# Microcontroller.net
KiCad netlist of a schematic drawn in Altium Designer
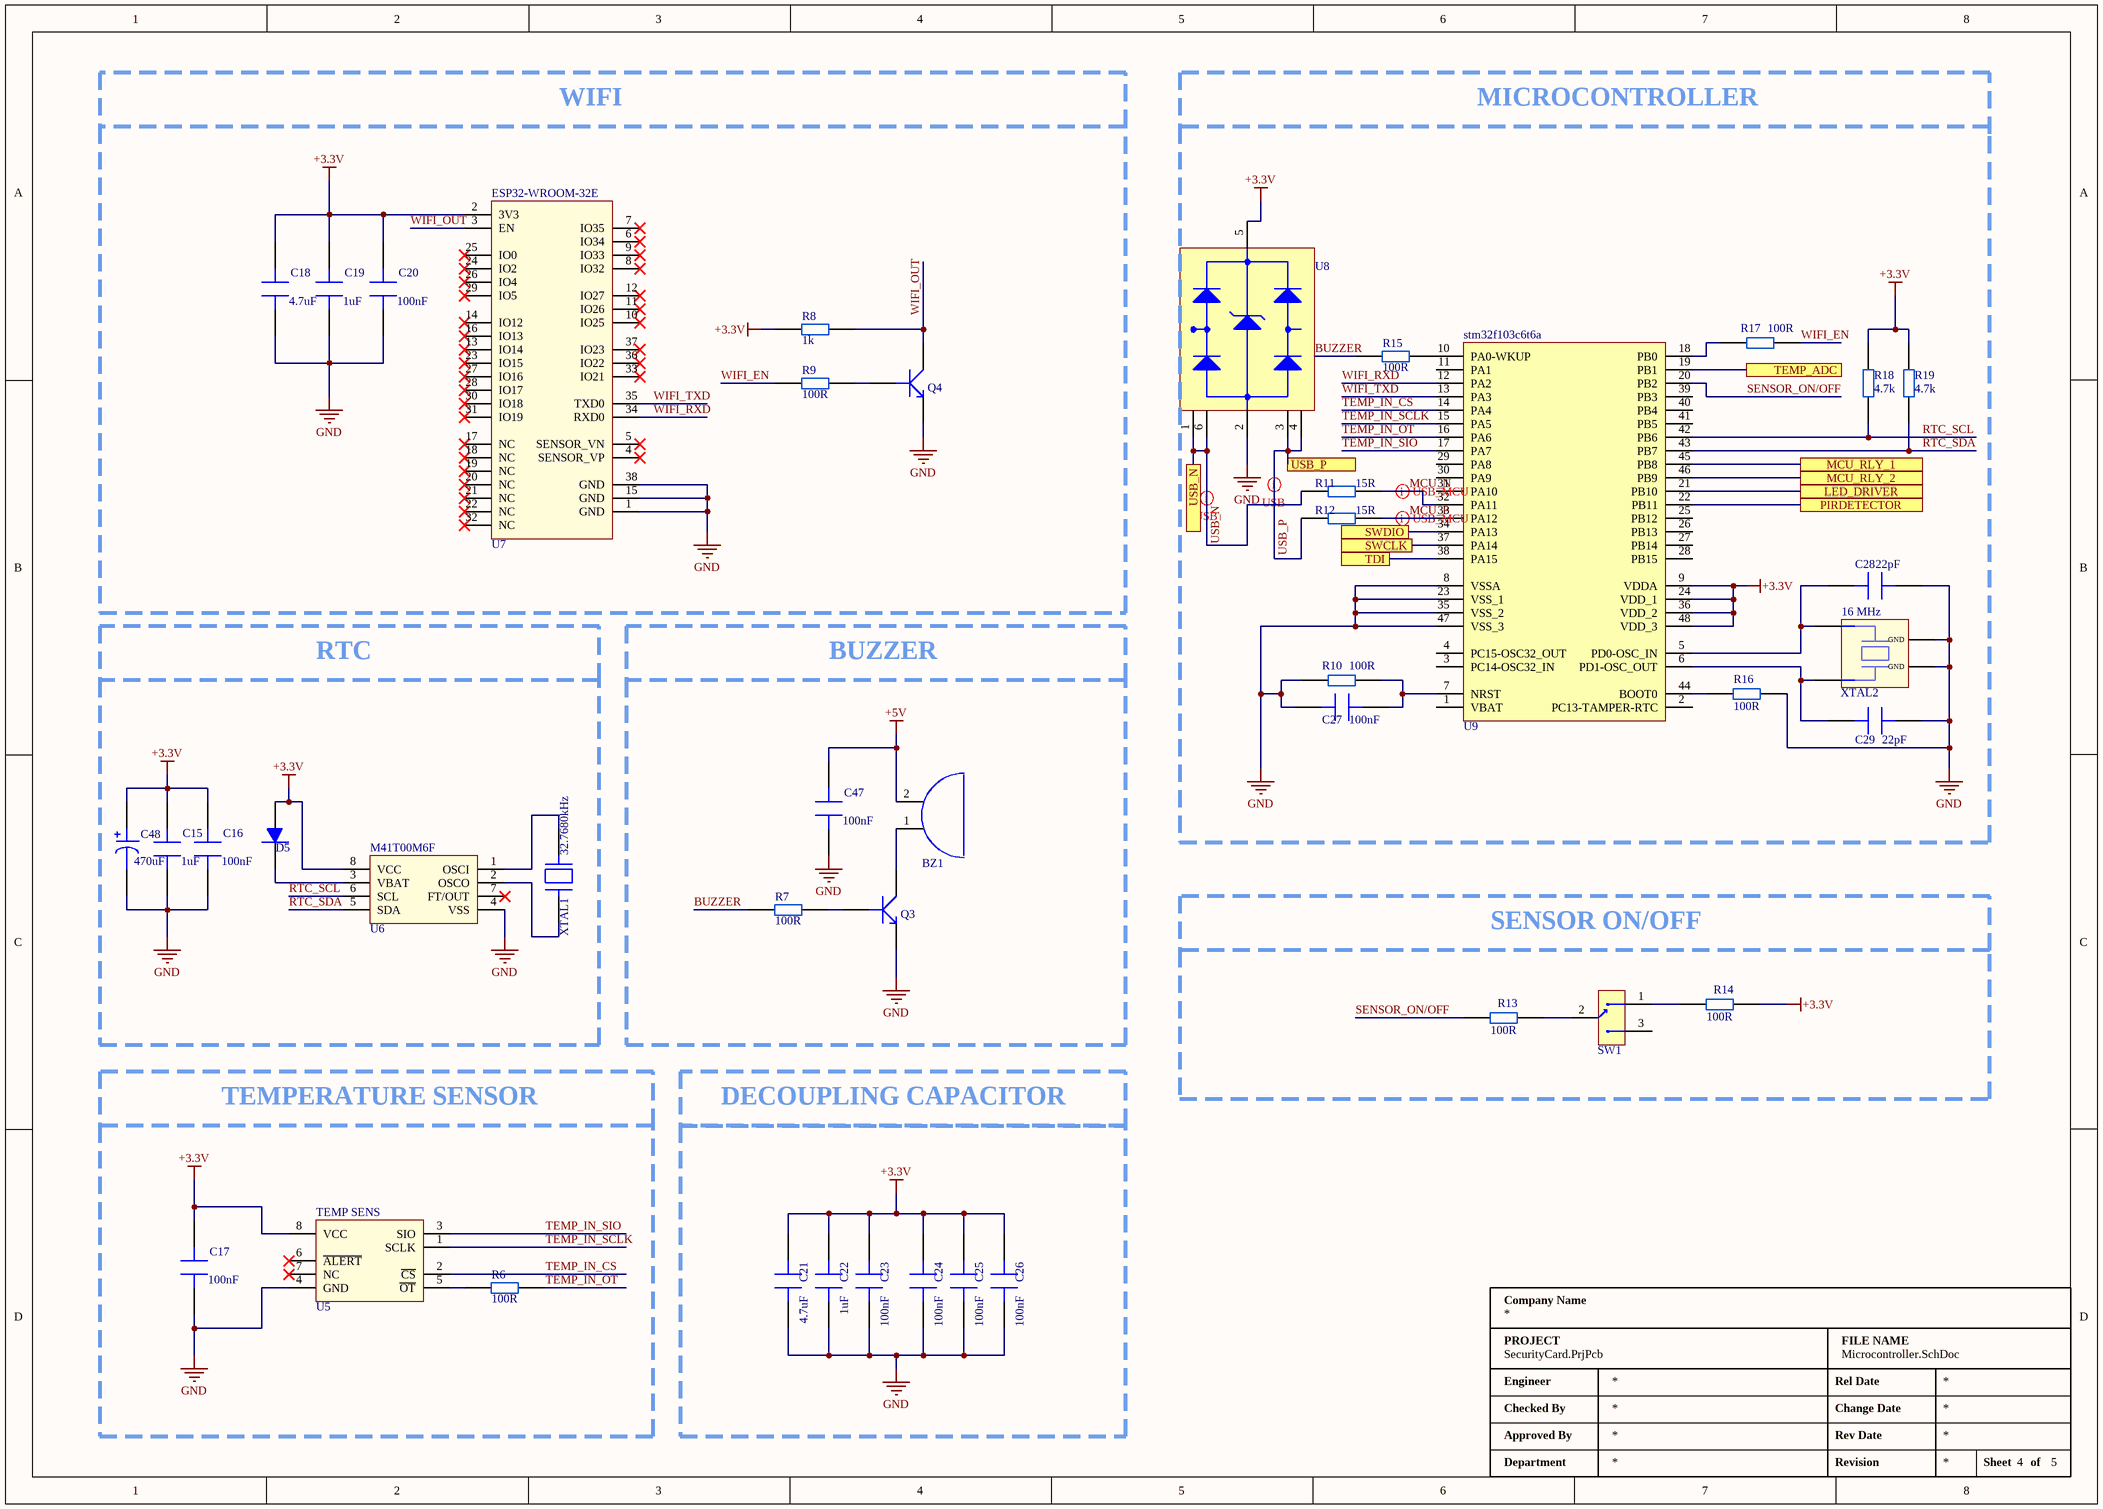
[diagram p0: Microcontroller.SchDoc]

(export (version "E")
  (design (tool "Eeschema 10.0.6"))
  (components
    (comp (ref "BZ1")
      (value "CMI-9605-0580T")
      (footprint "BUZZER")
      (description "9.6 mm, 5 Vdc, 80 dB, Through Hole, Driving Circuit, Magnetic Audio Indicator Buzzer")
      (fields (field (name "MANUFACTURER") "CUI") (field (name "DESIGNED BY") "SEFA"))
      (libsource (lib "SecurityLibray") (part "CMI-9605-0580T"))
    )
    (comp (ref "C15")
      (value "1uF")
      (footprint "CAP 0805")
      (description "Multilayer Ceramic Capacitor, 1 uF, 25 V, ï¿½ 10%, X7R, 0805 [2012 Metric]")
      (fields
        (field (name "MANUFACTURER") "KEMET")
        (field (name "MANUFACTURER PART NUMBER") "C0805C105K3RACTU")
      )
      (libsource (lib "SecurityLibray") (part "CAP MLCC 1uF 0805 MLCC"))
    )
    (comp (ref "C16")
      (value "100nF")
      (footprint "CAP 0805")
      (description "Multilayer Ceramic Capacitor, 0.1 uF, 50 V, ± 10%, X7R, 0805 [2012 Metric]")
      (fields
        (field (name "MANUFACTURER") "Yageo")
        (field (name "MANUFACTURER PART NUMBER") "CC0805KRX7R9BB104")
      )
      (libsource (lib "SecurityLibray") (part "CAP MLCC 100nF 0805"))
    )
    (comp (ref "C17")
      (value "100nF")
      (footprint "CAP 0603")
      (description "Multilayer Ceramic Capacitor, 0.1 uF, 50 V, ± 10%, X7R, 0603 [1608 Metric]")
      (fields
        (field (name "MANUFACTURER") "Kyocera AVX")
        (field (name "MANUFACTURER PART NUMBER") "06035C104K4T2A")
        (field (name "DESIGNED BY") "SEFA")
      )
      (libsource (lib "SecurityLibray") (part "CAP MLCC 100nF 0603"))
    )
    (comp (ref "C18")
      (value "4.7uF")
      (footprint "CAP 0805")
      (description "Multilayer Ceramic Capacitor, 4.7 uF, 25 V, ± 10%, X5R, 0805 [2012 Metric]")
      (fields
        (field (name "MANUFACTURER") "Samsung")
        (field (name "MANUFACTURER PART NUMBER") "CL21A475KAQNNNE")
        (field (name "DESIGNED BY") "SEFA")
      )
      (libsource (lib "SecurityLibray") (part "CAP MLCC 4.7uF 0805 MLCC"))
    )
    (comp (ref "C19")
      (value "1uF")
      (footprint "CAP 0805")
      (description "Multilayer Ceramic Capacitor, 1 uF, 25 V, ï¿½ 10%, X7R, 0805 [2012 Metric]")
      (fields
        (field (name "MANUFACTURER") "KEMET")
        (field (name "MANUFACTURER PART NUMBER") "C0805C105K3RACTU")
      )
      (libsource (lib "SecurityLibray") (part "CAP MLCC 1uF 0805 MLCC"))
    )
    (comp (ref "C20")
      (value "100nF")
      (footprint "CAP 0805")
      (description "Multilayer Ceramic Capacitor, 0.1 uF, 50 V, ± 10%, X7R, 0805 [2012 Metric]")
      (fields
        (field (name "MANUFACTURER") "Yageo")
        (field (name "MANUFACTURER PART NUMBER") "CC0805KRX7R9BB104")
      )
      (libsource (lib "SecurityLibray") (part "CAP MLCC 100nF 0805"))
    )
    (comp (ref "C21")
      (value "4.7uF")
      (footprint "CAP 0805")
      (description "Multilayer Ceramic Capacitor, 4.7 uF, 25 V, ± 10%, X5R, 0805 [2012 Metric]")
      (fields
        (field (name "MANUFACTURER") "Samsung")
        (field (name "MANUFACTURER PART NUMBER") "CL21A475KAQNNNE")
        (field (name "DESIGNED BY") "SEFA")
      )
      (libsource (lib "SecurityLibray") (part "CAP MLCC 4.7uF 0805 MLCC"))
    )
    (comp (ref "C22")
      (value "1uF")
      (footprint "CAP 0805")
      (description "Multilayer Ceramic Capacitor, 1 uF, 25 V, ï¿½ 10%, X7R, 0805 [2012 Metric]")
      (fields
        (field (name "MANUFACTURER") "KEMET")
        (field (name "MANUFACTURER PART NUMBER") "C0805C105K3RACTU")
      )
      (libsource (lib "SecurityLibray") (part "CAP MLCC 1uF 0805 MLCC"))
    )
    (comp (ref "C23")
      (value "100nF")
      (footprint "CAP 0805")
      (description "Multilayer Ceramic Capacitor, 0.1 uF, 50 V, ± 10%, X7R, 0805 [2012 Metric]")
      (fields
        (field (name "MANUFACTURER") "Yageo")
        (field (name "MANUFACTURER PART NUMBER") "CC0805KRX7R9BB104")
      )
      (libsource (lib "SecurityLibray") (part "CAP MLCC 100nF 0805"))
    )
    (comp (ref "C24")
      (value "100nF")
      (footprint "CAP 0805")
      (description "Multilayer Ceramic Capacitor, 0.1 uF, 50 V, ± 10%, X7R, 0805 [2012 Metric]")
      (fields
        (field (name "MANUFACTURER") "Yageo")
        (field (name "MANUFACTURER PART NUMBER") "CC0805KRX7R9BB104")
      )
      (libsource (lib "SecurityLibray") (part "CAP MLCC 100nF 0805"))
    )
    (comp (ref "C25")
      (value "100nF")
      (footprint "CAP 0805")
      (description "Multilayer Ceramic Capacitor, 0.1 uF, 50 V, ± 10%, X7R, 0805 [2012 Metric]")
      (fields
        (field (name "MANUFACTURER") "Yageo")
        (field (name "MANUFACTURER PART NUMBER") "CC0805KRX7R9BB104")
      )
      (libsource (lib "SecurityLibray") (part "CAP MLCC 100nF 0805"))
    )
    (comp (ref "C26")
      (value "100nF")
      (footprint "CAP 0805")
      (description "Multilayer Ceramic Capacitor, 0.1 uF, 50 V, ± 10%, X7R, 0805 [2012 Metric]")
      (fields
        (field (name "MANUFACTURER") "Yageo")
        (field (name "MANUFACTURER PART NUMBER") "CC0805KRX7R9BB104")
      )
      (libsource (lib "SecurityLibray") (part "CAP MLCC 100nF 0805"))
    )
    (comp (ref "C27")
      (value "100nF")
      (footprint "CAP 0805")
      (description "Multilayer Ceramic Capacitor, 0.1 uF, 50 V, ± 10%, X7R, 0805 [2012 Metric]")
      (fields
        (field (name "MANUFACTURER") "Yageo")
        (field (name "MANUFACTURER PART NUMBER") "CC0805KRX7R9BB104")
      )
      (libsource (lib "SecurityLibray") (part "CAP MLCC 100nF 0805"))
    )
    (comp (ref "C28")
      (value "22pF")
      (footprint "CAP 0603")
      (description "Multilayer Ceramic Capacitor, 22 pF, 50 V, ï¿½ 5%, C0G (NP0), 0603 [1608 Metric]")
      (fields
        (field (name "MANUFACTURER") "KEMET")
        (field (name "MANUFACTURER PART NUMBER") "C0603C220J5GACTU")
        (field (name "DESIGNED BY") "SEFA")
      )
      (libsource (lib "SecurityLibray") (part "CAP MLCC 22pF 0603"))
    )
    (comp (ref "C29")
      (value "22pF")
      (footprint "CAP 0603")
      (description "Multilayer Ceramic Capacitor, 22 pF, 50 V, ï¿½ 5%, C0G (NP0), 0603 [1608 Metric]")
      (fields
        (field (name "MANUFACTURER") "KEMET")
        (field (name "MANUFACTURER PART NUMBER") "C0603C220J5GACTU")
        (field (name "DESIGNED BY") "SEFA")
      )
      (libsource (lib "SecurityLibray") (part "CAP MLCC 22pF 0603"))
    )
    (comp (ref "C47")
      (value "100nF")
      (footprint "CAP 0805")
      (description "Multilayer Ceramic Capacitor, 0.1 uF, 50 V, ± 10%, X7R, 0805 [2012 Metric]")
      (fields
        (field (name "MANUFACTURER") "Yageo")
        (field (name "MANUFACTURER PART NUMBER") "CC0805KRX7R9BB104")
      )
      (libsource (lib "SecurityLibray") (part "CAP MLCC 100nF 0805"))
    )
    (comp (ref "C48")
      (value "470uF")
      (footprint "CAP ALUM 470UF 20% 50V RADIAL TH")
      (description "Aluminum Electrolytic Capacitor, 470 uF, 63 V, ± 20%, 8000 hours @ 85°C, Axial Leaded")
      (fields
        (field (name "MANUFACTURER") "Vishay BCcomponents")
        (field (name "MANUFACTURER PART NUMBER") "MAL202118471E3")
      )
      (libsource (lib "SecurityLibray") (part "470uF ECAP CA-1HM471"))
    )
    (comp (ref "D5")
      (value "DIODE GEN PURP 75V 150MA SOD323F")
      (footprint "DIODE SOD323F")
      (description "Diode Ultra Fast Recovery Rectifier 75V 0.15A 2-Pin SOD-323F T/R")
      (fields
        (field (name "MANUFACTURER") "ON Semiconductor / Fairchild")
        (field (name "MANUFACTURER PART NUMBER") "1N4148WS")
      )
      (libsource (lib "SecurityLibray") (part "DIODE 1N4148WS"))
    )
    (comp (ref "Q3")
      (value "TRANS NPN 40V 0.2A SOT23")
      (footprint "SOT-23-3")
      (description "Transistor: NPN; bipolar; 40V; 0.2A; 350mW; -55+150 deg.C; SMD; SOT23")
      (fields
        (field (name "MANUFACTURER") "Diotec")
        (field (name "MANUFACTURER PART NUMBER") "MMBT3904")
        (field (name "DESIGNED BY") "SEFA")
      )
      (libsource (lib "SecurityLibray") (part "MMBT3904 NPN TR"))
    )
    (comp (ref "Q4")
      (value "TRANS NPN 40V 0.2A SOT23")
      (footprint "SOT-23-3")
      (description "Transistor: NPN; bipolar; 40V; 0.2A; 350mW; -55+150 deg.C; SMD; SOT23")
      (fields
        (field (name "MANUFACTURER") "Diotec")
        (field (name "MANUFACTURER PART NUMBER") "MMBT3904")
        (field (name "DESIGNED BY") "SEFA")
      )
      (libsource (lib "SecurityLibray") (part "MMBT3904 NPN TR"))
    )
    (comp (ref "R6")
      (value "100R")
      (footprint "RES 0603")
      (description "Res Thick Film 0603 10K Ohm 5% 1/10W ±100ppm/°C Molded SMD SMD Paper T/R")
      (fields
        (field (name "MANUFACTURER") "Stackpole Electronics")
        (field (name "MANUFACTURER PART NUMBER") "RMCF0603JT10K0")
        (field (name "DESIGNED BY") "SEFA")
      )
      (libsource (lib "SecurityLibray") (part "RES 10K OHM 0603"))
    )
    (comp (ref "R7")
      (value "100R")
      (footprint "RES 0603")
      (description "Res Thick Film 0603 10K Ohm 5% 1/10W ±100ppm/°C Molded SMD SMD Paper T/R")
      (fields
        (field (name "MANUFACTURER") "Stackpole Electronics")
        (field (name "MANUFACTURER PART NUMBER") "RMCF0603JT10K0")
        (field (name "DESIGNED BY") "SEFA")
      )
      (libsource (lib "SecurityLibray") (part "RES 10K OHM 0603"))
    )
    (comp (ref "R8")
      (value "1k")
      (footprint "RES 0603")
      (description "Res Thick Film 0603 10K Ohm 5% 1/10W ±100ppm/°C Molded SMD SMD Paper T/R")
      (fields
        (field (name "MANUFACTURER") "Stackpole Electronics")
        (field (name "MANUFACTURER PART NUMBER") "RMCF0603JT10K0")
        (field (name "DESIGNED BY") "SEFA")
      )
      (libsource (lib "") (part "RES 10K OHM 0603_2"))
    )
    (comp (ref "R9")
      (value "100R")
      (footprint "RES 0603")
      (description "Res Thick Film 0603 10K Ohm 5% 1/10W ±100ppm/°C Molded SMD SMD Paper T/R")
      (fields
        (field (name "MANUFACTURER") "Stackpole Electronics")
        (field (name "MANUFACTURER PART NUMBER") "RMCF0603JT10K0")
        (field (name "DESIGNED BY") "SEFA")
      )
      (libsource (lib "SecurityLibray") (part "RES 10K OHM 0603"))
    )
    (comp (ref "R10")
      (value "100R")
      (footprint "RES 0603")
      (description "Res Thick Film 0603 10K Ohm 5% 1/10W ±100ppm/°C Molded SMD SMD Paper T/R")
      (fields
        (field (name "MANUFACTURER") "Stackpole Electronics")
        (field (name "MANUFACTURER PART NUMBER") "RMCF0603JT10K0")
        (field (name "DESIGNED BY") "SEFA")
      )
      (libsource (lib "") (part "RES 10K OHM 0603_2"))
    )
    (comp (ref "R11")
      (value "15R")
      (footprint "RES 0603")
      (description "Res Thick Film 0603 15 Ohm 1% 0.1W(1/10W) ±100ppm/C Pad SMD Automotive T/R")
      (fields
        (field (name "MANUFACTURER") "Stackpole Electronics")
        (field (name "MANUFACTURER PART NUMBER") "RMCF0603FT15R0")
        (field (name "DESIGNED BY") "SEFA")
      )
      (libsource (lib "SecurityLibray") (part "RES 15R OHM 0603"))
    )
    (comp (ref "R12")
      (value "15R")
      (footprint "RES 0603")
      (description "Res Thick Film 0603 15 Ohm 1% 0.1W(1/10W) ±100ppm/C Pad SMD Automotive T/R")
      (fields
        (field (name "MANUFACTURER") "Stackpole Electronics")
        (field (name "MANUFACTURER PART NUMBER") "RMCF0603FT15R0")
        (field (name "DESIGNED BY") "SEFA")
      )
      (libsource (lib "SecurityLibray") (part "RES 15R OHM 0603"))
    )
    (comp (ref "R13")
      (value "100R")
      (footprint "RES 0603")
      (description "GENERAL PURPOSE CHIP RESISTOR Metal Glaze/thick Film, 0.1W, 0ohm, Surface Mount, 0603")
      (fields
        (field (name "MANUFACTURER") "Yageo")
        (field (name "MANUFACTURER PART NUMBER") "RC0603JR-070RL")
        (field (name "DESIGNED BY") "SEFA")
      )
      (libsource (lib "SecurityLibray") (part "RES 0R OHM 0603"))
    )
    (comp (ref "R14")
      (value "100R")
      (footprint "RES 0603")
      (description "GENERAL PURPOSE CHIP RESISTOR Metal Glaze/thick Film, 0.1W, 0ohm, Surface Mount, 0603")
      (fields
        (field (name "MANUFACTURER") "Yageo")
        (field (name "MANUFACTURER PART NUMBER") "RC0603JR-070RL")
        (field (name "DESIGNED BY") "SEFA")
      )
      (libsource (lib "SecurityLibray") (part "RES 0R OHM 0603"))
    )
    (comp (ref "R15")
      (value "100R")
      (footprint "RES 0603")
      (description "Res Thick Film 0603 10K Ohm 5% 1/10W ±100ppm/°C Molded SMD SMD Paper T/R")
      (fields
        (field (name "MANUFACTURER") "Stackpole Electronics")
        (field (name "MANUFACTURER PART NUMBER") "RMCF0603JT10K0")
        (field (name "DESIGNED BY") "SEFA")
      )
      (libsource (lib "SecurityLibray") (part "RES 10K OHM 0603"))
    )
    (comp (ref "R16")
      (value "100R")
      (footprint "RES 0603")
      (description "Res Thick Film 0603 10K Ohm 5% 1/10W ±100ppm/°C Molded SMD SMD Paper T/R")
      (fields
        (field (name "MANUFACTURER") "Stackpole Electronics")
        (field (name "MANUFACTURER PART NUMBER") "RMCF0603JT10K0")
        (field (name "DESIGNED BY") "SEFA")
      )
      (libsource (lib "") (part "RES 10K OHM 0603_2"))
    )
    (comp (ref "R17")
      (value "100R")
      (footprint "RES 0603")
      (description "Res Thick Film 0603 10K Ohm 5% 1/10W ±100ppm/°C Molded SMD SMD Paper T/R")
      (fields
        (field (name "MANUFACTURER") "Stackpole Electronics")
        (field (name "MANUFACTURER PART NUMBER") "RMCF0603JT10K0")
        (field (name "DESIGNED BY") "SEFA")
      )
      (libsource (lib "") (part "RES 10K OHM 0603_2"))
    )
    (comp (ref "R18")
      (value "4.7k")
      (footprint "RES 0603")
      (description "Res Thick Film 0603 10K Ohm 5% 1/10W ±100ppm/°C Molded SMD SMD Paper T/R")
      (fields
        (field (name "MANUFACTURER") "Stackpole Electronics")
        (field (name "MANUFACTURER PART NUMBER") "RMCF0603JT10K0")
        (field (name "DESIGNED BY") "SEFA")
      )
      (libsource (lib "") (part "RES 10K OHM 0603_1"))
    )
    (comp (ref "R19")
      (value "4.7k")
      (footprint "RES 0603")
      (description "Res Thick Film 0603 10K Ohm 5% 1/10W ±100ppm/°C Molded SMD SMD Paper T/R")
      (fields
        (field (name "MANUFACTURER") "Stackpole Electronics")
        (field (name "MANUFACTURER PART NUMBER") "RMCF0603JT10K0")
        (field (name "DESIGNED BY") "SEFA")
      )
      (libsource (lib "") (part "RES 10K OHM 0603_1"))
    )
    (comp (ref "SW1")
      (value "EG1215AA")
      (footprint "EG1215AA")
      (description "Slide Switch, SPDT, 0.025A, 24V, SMD")
      (fields (field (name "MANUFACTURER") "E-Switch") (field (name "DESIGNED BY") "SEFA"))
      (libsource (lib "SecurityLibray") (part "EG1215AA"))
    )
    (comp (ref "U5")
      (value "TEMP SENS")
      (footprint "SOIC8")
      (description "Temp Sensor Digital Serial (3-Wire, SPI) 8-Pin SOIC N Tube")
      (fields
        (field (name "MANUFACTURER") "Maxim")
        (field (name "MANUFACTURER PART NUMBER") "MAX6662MSA+")
        (field (name "DESIGNED BY") "SEFA")
      )
      (libsource (lib "SecurityLibray") (part "MAX6662"))
    )
    (comp (ref "U6")
      (value "M41T00M6F")
      (footprint "SOIC8")
      (description "Low-power serial real-time clock (RTC) with built-in battery switchover circuit")
      (fields
        (field (name "MANUFACTURER") "STMicroelectronics")
        (field (name "MANUFACTURER PART NUMBER") "M41T01M6F")
        (field (name "DESIGNED BY") "SEFA")
      )
      (libsource (lib "SecurityLibray") (part "M41T00M6F"))
    )
    (comp (ref "U7")
      (value "ESP32-WROOM-32E")
      (footprint "ESP32 WROOM 4MB")
      (description "SMD module, ESP32-D0WD-V3, ESP32 ECO V3, 4 MB SPI flash, PCB antenna")
      (fields
        (field (name "MANUFACTURER") "Espressif Systems")
        (field (name "MANUFACTURER PART NUMBER") "ESP32-WROOM-32E(M113EH3200PH3Q0)")
        (field (name "DESIGNED BY") "SEFA")
      )
      (libsource (lib "SecurityLibray") (part "ESP32-WROOM-32E(4MB)"))
    )
    (comp (ref "U8")
      (value "TVS DIODE 5.25VWM 17VC SOT23-6")
      (footprint "SOT23-6")
      (description "ESD Suppressor Diode Arrays Uni-Dir 15kV@Air Gap/8kV@Contact Disc 6-Pin SOT-23 T/R")
      (fields
        (field (name "MANUFACTURER") "STMicroelectronics")
        (field (name "MANUFACTURER PART NUMBER") "USBLC6-2SC6Y")
        (field (name "DESIGNED BY") "SEFA")
      )
      (libsource (lib "SecurityLibray") (part "DIODE TVS USB PRODECTION"))
    )
    (comp (ref "U9")
      (value "stm32f103c6t6a")
      (footprint "LQFP-48")
      (description "MCU 32-bit STM32F ARM Cortex M3 RISC 32KB Flash 2.5V/3.3V 48-Pin LQFP Tray")
      (fields
        (field (name "MANUFACTURER") "STMicroelectronics")
        (field (name "MANUFACTURER PART NUMBER") "STM32F103C6T6A")
        (field (name "DESIGNED BY") "SEFA")
      )
      (libsource (lib "SecurityLibray") (part "stm32f103c6t6a"))
    )
    (comp (ref "XTAL1")
      (value "32.7680kHz")
      (footprint "CRYSTALL 2SMD")
      (description "Crystal 0.032768MHz ±20ppm (Tol) 12.5pF Flexural 90000Ohm 2-Pin CSMD T/R")
      (fields
        (field (name "MANUFACTURER") "Abracon")
        (field (name "MANUFACTURER PART NUMBER") "ABS05-32.768KHZ-T")
        (field (name "DESIGNED BY") "SEFA")
      )
      (libsource (lib "SecurityLibray") (part "RTC CRYS ABS05-32.768KHZ-T"))
    )
    (comp (ref "XTAL2")
      (value "16 MHz")
      (footprint "CRYSTAL 16MHz 4SMD")
      (description "Crystal 16MHz ±30ppm (Tol) ±50ppm (Stability) 20pF FUND 50Ohm 4-Pin Mini-SMD T/R")
      (fields
        (field (name "MANUFACTURER") "ECS International")
        (field (name "MANUFACTURER PART NUMBER") "ECS-160-20-30B-TR")
        (field (name "DESIGNED BY") "SEFA")
      )
      (libsource (lib "SecurityLibray") (part "CRYSTAL 16MHz ECS-160-20-30B-TR"))
    )
  )
  (nets
    (net (code "1") (name "+3.3V") (class "Default")
      (node (ref "C15") (pin "2") (pinfunction "2_2") (pintype "passive"))
      (node (ref "C16") (pin "2") (pinfunction "2_2") (pintype "passive"))
      (node (ref "C17") (pin "2") (pinfunction "2_2") (pintype "passive"))
      (node (ref "C18") (pin "2") (pinfunction "2_2") (pintype "passive"))
      (node (ref "C19") (pin "2") (pinfunction "2_2") (pintype "passive"))
      (node (ref "C20") (pin "2") (pinfunction "2_2") (pintype "passive"))
      (node (ref "C21") (pin "2") (pinfunction "2_2") (pintype "passive"))
      (node (ref "C22") (pin "2") (pinfunction "2_2") (pintype "passive"))
      (node (ref "C23") (pin "2") (pinfunction "2_2") (pintype "passive"))
      (node (ref "C24") (pin "2") (pinfunction "2_2") (pintype "passive"))
      (node (ref "C25") (pin "2") (pinfunction "2_2") (pintype "passive"))
      (node (ref "C26") (pin "2") (pinfunction "2_2") (pintype "passive"))
      (node (ref "C48") (pin "1") (pinfunction "1_1") (pintype "passive"))
      (node (ref "D5") (pin "A") (pinfunction "1_A") (pintype "passive"))
      (node (ref "R14") (pin "2") (pinfunction "2_2") (pintype "passive"))
      (node (ref "R18") (pin "2") (pinfunction "2_2") (pintype "passive"))
      (node (ref "R19") (pin "2") (pinfunction "2_2") (pintype "passive"))
      (node (ref "R8") (pin "2") (pinfunction "2_2") (pintype "passive"))
      (node (ref "U5") (pin "8") (pinfunction "VCC_8") (pintype "passive"))
      (node (ref "U6") (pin "8") (pinfunction "VCC_8") (pintype "passive"))
      (node (ref "U7") (pin "2") (pinfunction "3V3_2") (pintype "passive"))
      (node (ref "U8") (pin "5") (pinfunction "VBUS_5") (pintype "power_in"))
      (node (ref "U9") (pin "24") (pinfunction "VDD_1_24") (pintype "passive"))
      (node (ref "U9") (pin "36") (pinfunction "VDD_2_36") (pintype "passive"))
      (node (ref "U9") (pin "48") (pinfunction "VDD_3_48") (pintype "passive"))
      (node (ref "U9") (pin "9") (pinfunction "VDDA_9") (pintype "passive"))
    )
    (net (code "2") (name "+5V") (class "Default")
      (node (ref "BZ1") (pin "2") (pinfunction "2_2") (pintype "passive"))
      (node (ref "C47") (pin "2") (pinfunction "2_2") (pintype "passive"))
    )
    (net (code "3") (name "/BUZZER") (class "Default")
      (node (ref "R15") (pin "1") (pinfunction "1_1") (pintype "passive"))
      (node (ref "R7") (pin "1") (pinfunction "1_1") (pintype "passive"))
    )
    (net (code "4") (name "/LED_DRIVER") (class "Default")
      (node (ref "U9") (pin "21") (pinfunction "PB10_21") (pintype "passive"))
    )
    (net (code "5") (name "/MCU_N") (class "Default")
      (node (ref "R11") (pin "2") (pinfunction "2_2") (pintype "passive"))
      (node (ref "U9") (pin "32") (pinfunction "PA11_32") (pintype "passive"))
    )
    (net (code "6") (name "/MCU_P") (class "Default")
      (node (ref "R12") (pin "2") (pinfunction "2_2") (pintype "passive"))
      (node (ref "U9") (pin "33") (pinfunction "PA12_33") (pintype "passive"))
    )
    (net (code "7") (name "/MCU_RLY_1") (class "Default")
      (node (ref "U9") (pin "45") (pinfunction "PB8_45") (pintype "passive"))
    )
    (net (code "8") (name "/MCU_RLY_2") (class "Default")
      (node (ref "U9") (pin "46") (pinfunction "PB9_46") (pintype "passive"))
    )
    (net (code "9") (name "/PIRDETECTOR") (class "Default")
      (node (ref "U9") (pin "22") (pinfunction "PB11_22") (pintype "passive"))
    )
    (net (code "10") (name "/RTC_SCL") (class "Default")
      (node (ref "R18") (pin "1") (pinfunction "1_1") (pintype "passive"))
      (node (ref "U6") (pin "6") (pinfunction "SCL_6") (pintype "passive"))
      (node (ref "U9") (pin "42") (pinfunction "PB6_42") (pintype "passive"))
    )
    (net (code "11") (name "/RTC_SDA") (class "Default")
      (node (ref "R19") (pin "1") (pinfunction "1_1") (pintype "passive"))
      (node (ref "U6") (pin "5") (pinfunction "SDA_5") (pintype "passive"))
      (node (ref "U9") (pin "43") (pinfunction "PB7_43") (pintype "passive"))
    )
    (net (code "12") (name "/SENSOR_ON{slash}OFF") (class "Default")
      (node (ref "R13") (pin "1") (pinfunction "1_1") (pintype "passive"))
      (node (ref "U9") (pin "20") (pinfunction "PB2_20") (pintype "passive"))
    )
    (net (code "13") (name "/SWCLK") (class "Default")
      (node (ref "U9") (pin "37") (pinfunction "PA14_37") (pintype "passive"))
    )
    (net (code "14") (name "/SWDIO") (class "Default")
      (node (ref "U9") (pin "34") (pinfunction "PA13_34") (pintype "passive"))
    )
    (net (code "15") (name "/TDI") (class "Default")
      (node (ref "U9") (pin "38") (pinfunction "PA15_38") (pintype "passive"))
    )
    (net (code "16") (name "/TEMP_ADC") (class "Default")
      (node (ref "U9") (pin "19") (pinfunction "PB1_19") (pintype "passive"))
    )
    (net (code "17") (name "/TEMP_IN_CS") (class "Default")
      (node (ref "U5") (pin "2") (pinfunction "~{CS}_2") (pintype "passive"))
      (node (ref "U9") (pin "14") (pinfunction "PA4_14") (pintype "passive"))
    )
    (net (code "18") (name "/TEMP_IN_OT") (class "Default")
      (node (ref "R6") (pin "2") (pinfunction "2_2") (pintype "passive"))
      (node (ref "U9") (pin "16") (pinfunction "PA6_16") (pintype "passive"))
    )
    (net (code "19") (name "/TEMP_IN_SCLK") (class "Default")
      (node (ref "U5") (pin "1") (pinfunction "SCLK_1") (pintype "passive"))
      (node (ref "U9") (pin "15") (pinfunction "PA5_15") (pintype "passive"))
    )
    (net (code "20") (name "/TEMP_IN_SIO") (class "Default")
      (node (ref "U5") (pin "3") (pinfunction "SIO_3") (pintype "passive"))
      (node (ref "U9") (pin "17") (pinfunction "PA7_17") (pintype "passive"))
    )
    (net (code "21") (name "/USB_N") (class "Default")
      (node (ref "R11") (pin "1") (pinfunction "1_1") (pintype "passive"))
      (node (ref "U8") (pin "1") (pinfunction "I/O1_IN_1") (pintype "passive"))
      (node (ref "U8") (pin "6") (pinfunction "I/O1_OUT_6") (pintype "passive"))
    )
    (net (code "22") (name "/USB_P") (class "Default")
      (node (ref "R12") (pin "1") (pinfunction "1_1") (pintype "passive"))
      (node (ref "U8") (pin "3") (pinfunction "I/O2_IN_3") (pintype "passive"))
      (node (ref "U8") (pin "4") (pinfunction "I/O2_OUT_4") (pintype "passive"))
    )
    (net (code "23") (name "/WIFI_EN") (class "Default")
      (node (ref "R17") (pin "1") (pinfunction "1_1") (pintype "passive"))
      (node (ref "R9") (pin "1") (pinfunction "1_1") (pintype "passive"))
    )
    (net (code "24") (name "/WIFI_OUT") (class "Default")
      (node (ref "Q4") (pin "3") (pinfunction "C_3") (pintype "passive"))
      (node (ref "R8") (pin "1") (pinfunction "1_1") (pintype "passive"))
      (node (ref "U7") (pin "3") (pinfunction "EN_3") (pintype "passive"))
    )
    (net (code "25") (name "/WIFI_RXD") (class "Default")
      (node (ref "U7") (pin "34") (pinfunction "RXD0_34") (pintype "passive"))
      (node (ref "U9") (pin "12") (pinfunction "PA2_12") (pintype "passive"))
    )
    (net (code "26") (name "/WIFI_TXD") (class "Default")
      (node (ref "U7") (pin "35") (pinfunction "TXD0_35") (pintype "passive"))
      (node (ref "U9") (pin "13") (pinfunction "PA3_13") (pintype "passive"))
    )
    (net (code "27") (name "GND") (class "Default")
      (node (ref "C15") (pin "1") (pinfunction "1_1") (pintype "passive"))
      (node (ref "C16") (pin "1") (pinfunction "1_1") (pintype "passive"))
      (node (ref "C17") (pin "1") (pinfunction "1_1") (pintype "passive"))
      (node (ref "C18") (pin "1") (pinfunction "1_1") (pintype "passive"))
      (node (ref "C19") (pin "1") (pinfunction "1_1") (pintype "passive"))
      (node (ref "C20") (pin "1") (pinfunction "1_1") (pintype "passive"))
      (node (ref "C21") (pin "1") (pinfunction "1_1") (pintype "passive"))
      (node (ref "C22") (pin "1") (pinfunction "1_1") (pintype "passive"))
      (node (ref "C23") (pin "1") (pinfunction "1_1") (pintype "passive"))
      (node (ref "C24") (pin "1") (pinfunction "1_1") (pintype "passive"))
      (node (ref "C25") (pin "1") (pinfunction "1_1") (pintype "passive"))
      (node (ref "C26") (pin "1") (pinfunction "1_1") (pintype "passive"))
      (node (ref "C27") (pin "1") (pinfunction "1_1") (pintype "passive"))
      (node (ref "C28") (pin "1") (pinfunction "1_1") (pintype "passive"))
      (node (ref "C29") (pin "1") (pinfunction "1_1") (pintype "passive"))
      (node (ref "C47") (pin "1") (pinfunction "1_1") (pintype "passive"))
      (node (ref "C48") (pin "2") (pinfunction "2_2") (pintype "passive"))
      (node (ref "Q3") (pin "2") (pinfunction "E_2") (pintype "passive"))
      (node (ref "Q4") (pin "2") (pinfunction "E_2") (pintype "passive"))
      (node (ref "R10") (pin "2") (pinfunction "2_2") (pintype "passive"))
      (node (ref "R16") (pin "1") (pinfunction "1_1") (pintype "passive"))
      (node (ref "U5") (pin "4") (pinfunction "GND_4") (pintype "passive"))
      (node (ref "U6") (pin "4") (pinfunction "VSS_4") (pintype "passive"))
      (node (ref "U7") (pin "1") (pinfunction "GND_1") (pintype "passive"))
      (node (ref "U7") (pin "15") (pinfunction "GND_15") (pintype "passive"))
      (node (ref "U7") (pin "38") (pinfunction "GND_38") (pintype "passive"))
      (node (ref "U8") (pin "2") (pinfunction "GND_2") (pintype "power_in"))
      (node (ref "U9") (pin "23") (pinfunction "VSS_1_23") (pintype "passive"))
      (node (ref "U9") (pin "35") (pinfunction "VSS_2_35") (pintype "passive"))
      (node (ref "U9") (pin "47") (pinfunction "VSS_3_47") (pintype "passive"))
      (node (ref "U9") (pin "8") (pinfunction "VSSA_8") (pintype "passive"))
      (node (ref "XTAL2") (pin "2") (pinfunction "GND_2") (pintype "passive"))
      (node (ref "XTAL2") (pin "4") (pinfunction "GND_4") (pintype "passive"))
    )
    (net (code "28") (name "Net-(D5-2)") (class "Default")
      (node (ref "D5") (pin "C") (pinfunction "2_C") (pintype "passive"))
      (node (ref "U6") (pin "3") (pinfunction "VBAT_3") (pintype "passive"))
    )
    (net (code "29") (name "Net-(Q3-B)") (class "Default")
      (node (ref "Q3") (pin "1") (pinfunction "B_1") (pintype "passive"))
      (node (ref "R7") (pin "2") (pinfunction "2_2") (pintype "passive"))
    )
    (net (code "30") (name "Net-(Q3-C)") (class "Default")
      (node (ref "BZ1") (pin "1") (pinfunction "1_1") (pintype "passive"))
      (node (ref "Q3") (pin "3") (pinfunction "C_3") (pintype "passive"))
    )
    (net (code "31") (name "Net-(Q4-B)") (class "Default")
      (node (ref "Q4") (pin "1") (pinfunction "B_1") (pintype "passive"))
      (node (ref "R9") (pin "2") (pinfunction "2_2") (pintype "passive"))
    )
    (net (code "32") (name "Net-(R14-Pad1)") (class "Default")
      (node (ref "R14") (pin "1") (pinfunction "1_1") (pintype "passive"))
      (node (ref "SW1") (pin "1") (pinfunction "1_1") (pintype "passive"))
    )
    (net (code "33") (name "Net-(SW1-_2)") (class "Default")
      (node (ref "R13") (pin "2") (pinfunction "2_2") (pintype "passive"))
      (node (ref "SW1") (pin "2") (pinfunction "_2_2") (pintype "passive"))
    )
    (net (code "34") (name "Net-(U5-~{OT})") (class "Default")
      (node (ref "R6") (pin "1") (pinfunction "1_1") (pintype "passive"))
      (node (ref "U5") (pin "5") (pinfunction "~{OT}_5") (pintype "passive"))
    )
    (net (code "35") (name "Net-(U6-OSCI)") (class "Default")
      (node (ref "U6") (pin "1") (pinfunction "OSCI_1") (pintype "passive"))
      (node (ref "XTAL1") (pin "1") (pinfunction "1_1") (pintype "passive"))
    )
    (net (code "36") (name "Net-(U6-OSCO)") (class "Default")
      (node (ref "U6") (pin "2") (pinfunction "OSCO_2") (pintype "passive"))
      (node (ref "XTAL1") (pin "2") (pinfunction "2_2") (pintype "passive"))
    )
    (net (code "37") (name "Net-(U9-BOOT0)") (class "Default")
      (node (ref "R16") (pin "2") (pinfunction "2_2") (pintype "passive"))
      (node (ref "U9") (pin "44") (pinfunction "BOOT0_44") (pintype "passive"))
    )
    (net (code "38") (name "Net-(U9-NRST)") (class "Default")
      (node (ref "C27") (pin "2") (pinfunction "2_2") (pintype "passive"))
      (node (ref "R10") (pin "1") (pinfunction "1_1") (pintype "passive"))
      (node (ref "U9") (pin "7") (pinfunction "NRST_7") (pintype "passive"))
    )
    (net (code "39") (name "Net-(U9-PA0-WKUP)") (class "Default")
      (node (ref "R15") (pin "2") (pinfunction "2_2") (pintype "passive"))
      (node (ref "U9") (pin "10") (pinfunction "PA0-WKUP_10") (pintype "passive"))
    )
    (net (code "40") (name "Net-(U9-PB0)") (class "Default")
      (node (ref "R17") (pin "2") (pinfunction "2_2") (pintype "passive"))
      (node (ref "U9") (pin "18") (pinfunction "PB0_18") (pintype "passive"))
    )
    (net (code "41") (name "Net-(U9-PD0-OSC_IN)") (class "Default")
      (node (ref "C28") (pin "2") (pinfunction "2_2") (pintype "passive"))
      (node (ref "U9") (pin "5") (pinfunction "PD0-OSC_IN_5") (pintype "passive"))
      (node (ref "XTAL2") (pin "1") (pinfunction "IN/OUT_1") (pintype "passive"))
    )
    (net (code "42") (name "Net-(U9-PD1-OSC_OUT)") (class "Default")
      (node (ref "C29") (pin "2") (pinfunction "2_2") (pintype "passive"))
      (node (ref "U9") (pin "6") (pinfunction "PD1-OSC_OUT_6") (pintype "passive"))
      (node (ref "XTAL2") (pin "3") (pinfunction "OUT/IN_3") (pintype "passive"))
    )
    (net (code "43") (name "unconnected-(SW1-_3-Pad3)") (class "Default")
      (node (ref "SW1") (pin "3") (pinfunction "_3_3") (pintype "passive"))
    )
    (net (code "44") (name "unconnected-(U5-NC-Pad7)") (class "Default")
      (node (ref "U5") (pin "7") (pinfunction "NC_7") (pintype "passive+no_connect"))
    )
    (net (code "45") (name "unconnected-(U5-~{ALERT}-Pad6)") (class "Default")
      (node (ref "U5") (pin "6") (pinfunction "~{ALERT}_6") (pintype "passive+no_connect"))
    )
    (net (code "46") (name "unconnected-(U6-FT{slash}OUT-Pad7)") (class "Default")
      (node (ref "U6") (pin "7") (pinfunction "FT/OUT_7") (pintype "passive+no_connect"))
    )
    (net (code "47") (name "unconnected-(U7-IO0-Pad25)") (class "Default")
      (node (ref "U7") (pin "25") (pinfunction "IO0_25") (pintype "passive+no_connect"))
    )
    (net (code "48") (name "unconnected-(U7-IO2-Pad24)") (class "Default")
      (node (ref "U7") (pin "24") (pinfunction "IO2_24") (pintype "passive+no_connect"))
    )
    (net (code "49") (name "unconnected-(U7-IO4-Pad26)") (class "Default")
      (node (ref "U7") (pin "26") (pinfunction "IO4_26") (pintype "passive+no_connect"))
    )
    (net (code "50") (name "unconnected-(U7-IO5-Pad29)") (class "Default")
      (node (ref "U7") (pin "29") (pinfunction "IO5_29") (pintype "passive+no_connect"))
    )
    (net (code "51") (name "unconnected-(U7-IO12-Pad14)") (class "Default")
      (node (ref "U7") (pin "14") (pinfunction "IO12_14") (pintype "passive+no_connect"))
    )
    (net (code "52") (name "unconnected-(U7-IO13-Pad16)") (class "Default")
      (node (ref "U7") (pin "16") (pinfunction "IO13_16") (pintype "passive+no_connect"))
    )
    (net (code "53") (name "unconnected-(U7-IO14-Pad13)") (class "Default")
      (node (ref "U7") (pin "13") (pinfunction "IO14_13") (pintype "passive+no_connect"))
    )
    (net (code "54") (name "unconnected-(U7-IO15-Pad23)") (class "Default")
      (node (ref "U7") (pin "23") (pinfunction "IO15_23") (pintype "passive+no_connect"))
    )
    (net (code "55") (name "unconnected-(U7-IO16-Pad27)") (class "Default")
      (node (ref "U7") (pin "27") (pinfunction "IO16_27") (pintype "passive+no_connect"))
    )
    (net (code "56") (name "unconnected-(U7-IO17-Pad28)") (class "Default")
      (node (ref "U7") (pin "28") (pinfunction "IO17_28") (pintype "passive+no_connect"))
    )
    (net (code "57") (name "unconnected-(U7-IO18-Pad30)") (class "Default")
      (node (ref "U7") (pin "30") (pinfunction "IO18_30") (pintype "passive+no_connect"))
    )
    (net (code "58") (name "unconnected-(U7-IO19-Pad31)") (class "Default")
      (node (ref "U7") (pin "31") (pinfunction "IO19_31") (pintype "passive+no_connect"))
    )
    (net (code "59") (name "unconnected-(U7-IO21-Pad33)") (class "Default")
      (node (ref "U7") (pin "33") (pinfunction "IO21_33") (pintype "passive+no_connect"))
    )
    (net (code "60") (name "unconnected-(U7-IO22-Pad36)") (class "Default")
      (node (ref "U7") (pin "36") (pinfunction "IO22_36") (pintype "passive+no_connect"))
    )
    (net (code "61") (name "unconnected-(U7-IO23-Pad37)") (class "Default")
      (node (ref "U7") (pin "37") (pinfunction "IO23_37") (pintype "passive+no_connect"))
    )
    (net (code "62") (name "unconnected-(U7-IO25-Pad10)") (class "Default")
      (node (ref "U7") (pin "10") (pinfunction "IO25_10") (pintype "passive+no_connect"))
    )
    (net (code "63") (name "unconnected-(U7-IO26-Pad11)") (class "Default")
      (node (ref "U7") (pin "11") (pinfunction "IO26_11") (pintype "passive+no_connect"))
    )
    (net (code "64") (name "unconnected-(U7-IO27-Pad12)") (class "Default")
      (node (ref "U7") (pin "12") (pinfunction "IO27_12") (pintype "passive+no_connect"))
    )
    (net (code "65") (name "unconnected-(U7-IO32-Pad8)") (class "Default")
      (node (ref "U7") (pin "8") (pinfunction "IO32_8") (pintype "passive+no_connect"))
    )
    (net (code "66") (name "unconnected-(U7-IO33-Pad9)") (class "Default")
      (node (ref "U7") (pin "9") (pinfunction "IO33_9") (pintype "passive+no_connect"))
    )
    (net (code "67") (name "unconnected-(U7-IO34-Pad6)") (class "Default")
      (node (ref "U7") (pin "6") (pinfunction "IO34_6") (pintype "passive+no_connect"))
    )
    (net (code "68") (name "unconnected-(U7-IO35-Pad7)") (class "Default")
      (node (ref "U7") (pin "7") (pinfunction "IO35_7") (pintype "passive+no_connect"))
    )
    (net (code "69") (name "unconnected-(U7-NC-Pad17)") (class "Default")
      (node (ref "U7") (pin "17") (pinfunction "NC_17") (pintype "passive+no_connect"))
    )
    (net (code "70") (name "unconnected-(U7-NC-Pad18)") (class "Default")
      (node (ref "U7") (pin "18") (pinfunction "NC_18") (pintype "passive+no_connect"))
    )
    (net (code "71") (name "unconnected-(U7-NC-Pad19)") (class "Default")
      (node (ref "U7") (pin "19") (pinfunction "NC_19") (pintype "passive+no_connect"))
    )
    (net (code "72") (name "unconnected-(U7-NC-Pad20)") (class "Default")
      (node (ref "U7") (pin "20") (pinfunction "NC_20") (pintype "passive+no_connect"))
    )
    (net (code "73") (name "unconnected-(U7-NC-Pad21)") (class "Default")
      (node (ref "U7") (pin "21") (pinfunction "NC_21") (pintype "passive+no_connect"))
    )
    (net (code "74") (name "unconnected-(U7-NC-Pad22)") (class "Default")
      (node (ref "U7") (pin "22") (pinfunction "NC_22") (pintype "passive+no_connect"))
    )
    (net (code "75") (name "unconnected-(U7-NC-Pad32)") (class "Default")
      (node (ref "U7") (pin "32") (pinfunction "NC_32") (pintype "passive+no_connect"))
    )
    (net (code "76") (name "unconnected-(U7-SENSOR_VN-Pad5)") (class "Default")
      (node (ref "U7") (pin "5") (pinfunction "SENSOR_VN_5") (pintype "passive+no_connect"))
    )
    (net (code "77") (name "unconnected-(U7-SENSOR_VP-Pad4)") (class "Default")
      (node (ref "U7") (pin "4") (pinfunction "SENSOR_VP_4") (pintype "passive+no_connect"))
    )
    (net (code "78") (name "unconnected-(U9-PA1-Pad11)") (class "Default")
      (node (ref "U9") (pin "11") (pinfunction "PA1_11") (pintype "passive"))
    )
    (net (code "79") (name "unconnected-(U9-PA8-Pad29)") (class "Default")
      (node (ref "U9") (pin "29") (pinfunction "PA8_29") (pintype "passive"))
    )
    (net (code "80") (name "unconnected-(U9-PA9-Pad30)") (class "Default")
      (node (ref "U9") (pin "30") (pinfunction "PA9_30") (pintype "passive"))
    )
    (net (code "81") (name "unconnected-(U9-PA10-Pad31)") (class "Default")
      (node (ref "U9") (pin "31") (pinfunction "PA10_31") (pintype "passive"))
    )
    (net (code "82") (name "unconnected-(U9-PB3-Pad39)") (class "Default")
      (node (ref "U9") (pin "39") (pinfunction "PB3_39") (pintype "passive"))
    )
    (net (code "83") (name "unconnected-(U9-PB4-Pad40)") (class "Default")
      (node (ref "U9") (pin "40") (pinfunction "PB4_40") (pintype "passive"))
    )
    (net (code "84") (name "unconnected-(U9-PB5-Pad41)") (class "Default")
      (node (ref "U9") (pin "41") (pinfunction "PB5_41") (pintype "passive"))
    )
    (net (code "85") (name "unconnected-(U9-PB12-Pad25)") (class "Default")
      (node (ref "U9") (pin "25") (pinfunction "PB12_25") (pintype "passive"))
    )
    (net (code "86") (name "unconnected-(U9-PB13-Pad26)") (class "Default")
      (node (ref "U9") (pin "26") (pinfunction "PB13_26") (pintype "passive"))
    )
    (net (code "87") (name "unconnected-(U9-PB14-Pad27)") (class "Default")
      (node (ref "U9") (pin "27") (pinfunction "PB14_27") (pintype "passive"))
    )
    (net (code "88") (name "unconnected-(U9-PB15-Pad28)") (class "Default")
      (node (ref "U9") (pin "28") (pinfunction "PB15_28") (pintype "passive"))
    )
    (net (code "89") (name "unconnected-(U9-PC13-TAMPER-RTC-Pad2)") (class "Default")
      (node (ref "U9") (pin "2") (pinfunction "PC13-TAMPER-RTC_2") (pintype "passive"))
    )
    (net (code "90") (name "unconnected-(U9-PC14-OSC32_IN-Pad3)") (class "Default")
      (node (ref "U9") (pin "3") (pinfunction "PC14-OSC32_IN_3") (pintype "passive"))
    )
    (net (code "91") (name "unconnected-(U9-PC15-OSC32_OUT-Pad4)") (class "Default")
      (node (ref "U9") (pin "4") (pinfunction "PC15-OSC32_OUT_4") (pintype "passive"))
    )
    (net (code "92") (name "unconnected-(U9-VBAT-Pad1)") (class "Default")
      (node (ref "U9") (pin "1") (pinfunction "VBAT_1") (pintype "passive"))
    )
  )
)
